# W5500.net
KiCad netlist of a schematic drawn in Altium Designer
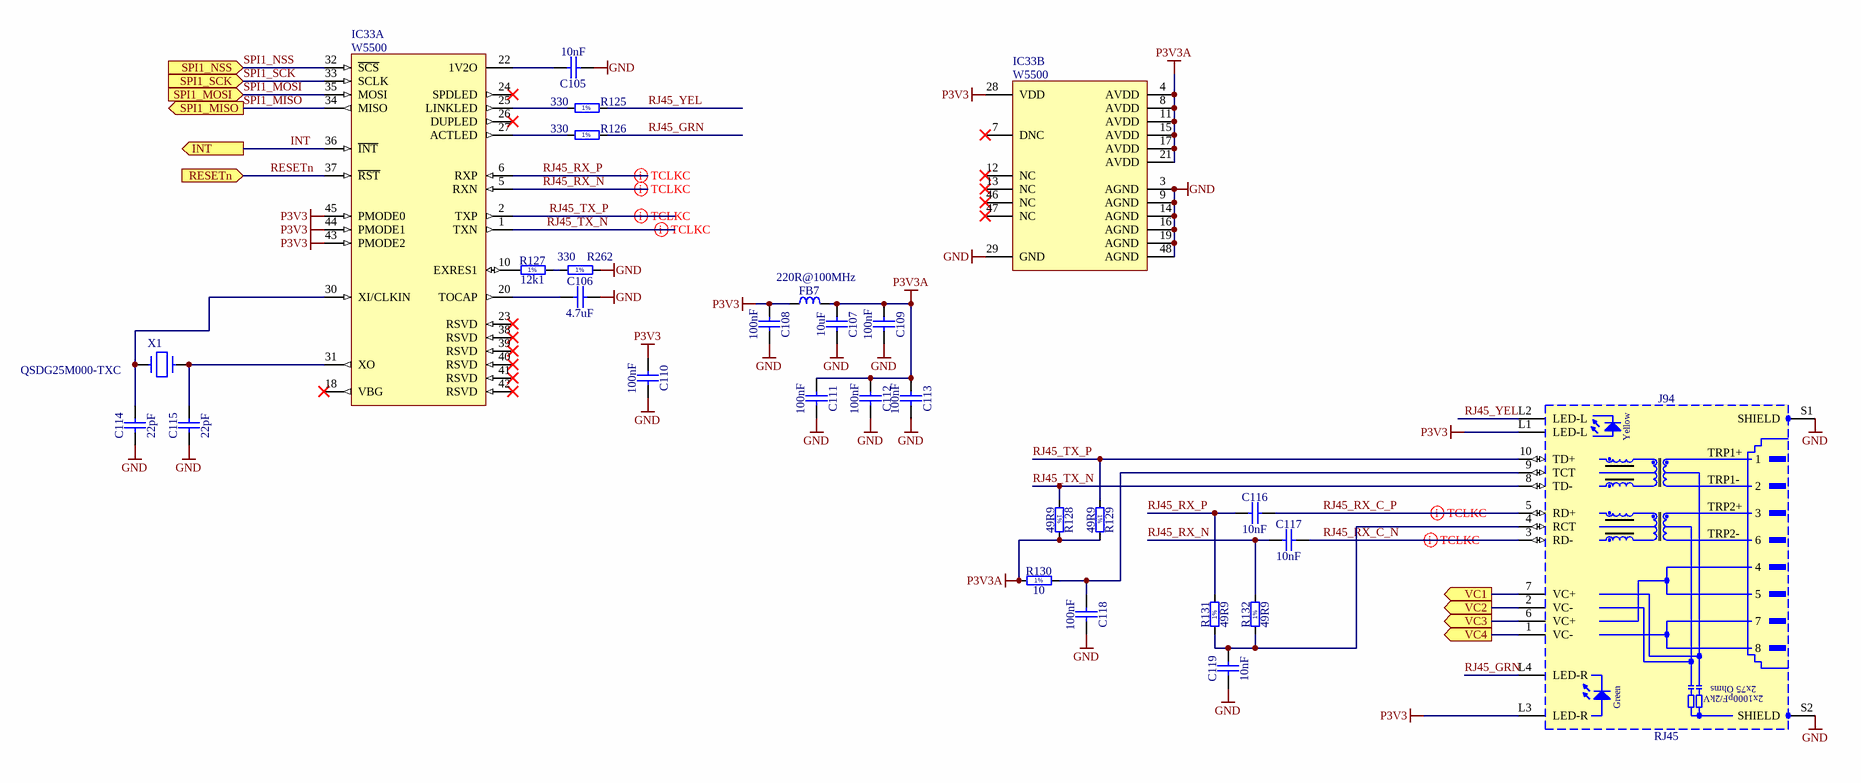
[diagram p0: W5500.SchDoc]

(export (version "E")
  (design (tool "Eeschema 10.0.6"))
  (components
    (comp (ref "C105")
      (value "10nF")
      (footprint "CAPC1608X87N")
      (description "Non-polarised capacitor")
      (fields
        (field (name "PART NUMBER") "CC0603_10NF_50V_5%_C0G")
        (field (name "VOLTAGE") "50V")
        (field (name "AUTHOR") "CERN DEM JLC")
      )
      (libsource (lib "Capacitors") (part "Capacitor - non polarized"))
    )
    (comp (ref "C106")
      (value "4.7uF")
      (footprint "CAPC1608X90N")
      (description "Non-polarised capacitor")
      (fields
        (field (name "PART NUMBER") "CC0603_4.7UF_25V_10%_X5R")
        (field (name "VOLTAGE") "25V")
        (field (name "AUTHOR") "CERN DEM JLC")
      )
      (libsource (lib "Capacitors") (part "Capacitor - non polarized"))
    )
    (comp (ref "C107")
      (value "10uF")
      (footprint "CAPC2012X135N")
      (description "Non-polarised capacitor")
      (fields
        (field (name "PART NUMBER") "CC0805_10UF_16V_10%_X5R")
        (field (name "VOLTAGE") "16V")
        (field (name "AUTHOR") "CERN DEM JLC")
      )
      (libsource (lib "Capacitors") (part "Capacitor - non polarized"))
    )
    (comp (ref "C108")
      (value "100nF")
      (footprint "CAPC1005X55N")
      (description "Non-polarised capacitor")
      (fields
        (field (name "PART NUMBER") "CC0402_100NF_16V_10%_X7R")
        (field (name "VOLTAGE") "16V")
        (field (name "AUTHOR") "CERN DEM JLC")
      )
      (libsource (lib "Capacitors") (part "Capacitor - non polarized"))
    )
    (comp (ref "C109")
      (value "100nF")
      (footprint "CAPC1005X55N")
      (description "Non-polarised capacitor")
      (fields
        (field (name "PART NUMBER") "CC0402_100NF_16V_10%_X7R")
        (field (name "VOLTAGE") "16V")
        (field (name "AUTHOR") "CERN DEM JLC")
      )
      (libsource (lib "Capacitors") (part "Capacitor - non polarized"))
    )
    (comp (ref "C110")
      (value "100nF")
      (footprint "CAPC1005X55N")
      (description "Non-polarised capacitor")
      (fields
        (field (name "PART NUMBER") "CC0402_100NF_16V_10%_X7R")
        (field (name "VOLTAGE") "16V")
        (field (name "AUTHOR") "CERN DEM JLC")
      )
      (libsource (lib "Capacitors") (part "Capacitor - non polarized"))
    )
    (comp (ref "C111")
      (value "100nF")
      (footprint "CAPC1005X55N")
      (description "Non-polarised capacitor")
      (fields
        (field (name "PART NUMBER") "CC0402_100NF_16V_10%_X7R")
        (field (name "VOLTAGE") "16V")
        (field (name "AUTHOR") "CERN DEM JLC")
      )
      (libsource (lib "Capacitors") (part "Capacitor - non polarized"))
    )
    (comp (ref "C112")
      (value "100nF")
      (footprint "CAPC1005X55N")
      (description "Non-polarised capacitor")
      (fields
        (field (name "PART NUMBER") "CC0402_100NF_16V_10%_X7R")
        (field (name "VOLTAGE") "16V")
        (field (name "AUTHOR") "CERN DEM JLC")
      )
      (libsource (lib "Capacitors") (part "Capacitor - non polarized"))
    )
    (comp (ref "C113")
      (value "100nF")
      (footprint "CAPC1005X55N")
      (description "Non-polarised capacitor")
      (fields
        (field (name "PART NUMBER") "CC0402_100NF_16V_10%_X7R")
        (field (name "VOLTAGE") "16V")
        (field (name "AUTHOR") "CERN DEM JLC")
      )
      (libsource (lib "Capacitors") (part "Capacitor - non polarized"))
    )
    (comp (ref "C114")
      (value "22pF")
      (footprint "CAPC1005X55N")
      (description "Non-polarised capacitor")
      (fields
        (field (name "PART NUMBER") "CC0402_22PF_50V_5%_NP0")
        (field (name "VOLTAGE") "50V")
        (field (name "AUTHOR") "CERN DEM JLC")
      )
      (libsource (lib "Capacitors") (part "Capacitor - non polarized"))
    )
    (comp (ref "C115")
      (value "22pF")
      (footprint "CAPC1005X55N")
      (description "Non-polarised capacitor")
      (fields
        (field (name "PART NUMBER") "CC0402_22PF_50V_5%_NP0")
        (field (name "VOLTAGE") "50V")
        (field (name "AUTHOR") "CERN DEM JLC")
      )
      (libsource (lib "Capacitors") (part "Capacitor - non polarized"))
    )
    (comp (ref "C116")
      (value "10nF")
      (footprint "CAPC1608X87N")
      (description "Non-polarised capacitor")
      (fields
        (field (name "PART NUMBER") "CC0603_10NF_50V_5%_C0G")
        (field (name "VOLTAGE") "50V")
        (field (name "AUTHOR") "CERN DEM JLC")
      )
      (libsource (lib "Capacitors") (part "Capacitor - non polarized"))
    )
    (comp (ref "C117")
      (value "10nF")
      (footprint "CAPC1608X87N")
      (description "Non-polarised capacitor")
      (fields
        (field (name "PART NUMBER") "CC0603_10NF_50V_5%_C0G")
        (field (name "VOLTAGE") "50V")
        (field (name "AUTHOR") "CERN DEM JLC")
      )
      (libsource (lib "Capacitors") (part "Capacitor - non polarized"))
    )
    (comp (ref "C118")
      (value "100nF")
      (footprint "CAPC1005X55N")
      (description "Non-polarised capacitor")
      (fields
        (field (name "PART NUMBER") "CC0402_100NF_16V_10%_X7R")
        (field (name "VOLTAGE") "16V")
        (field (name "AUTHOR") "CERN DEM JLC")
      )
      (libsource (lib "Capacitors") (part "Capacitor - non polarized"))
    )
    (comp (ref "C119")
      (value "10nF")
      (footprint "CAPC1608X87N")
      (description "Non-polarised capacitor")
      (fields
        (field (name "PART NUMBER") "CC0603_10NF_50V_5%_C0G")
        (field (name "VOLTAGE") "50V")
        (field (name "AUTHOR") "CERN DEM JLC")
      )
      (libsource (lib "Capacitors") (part "Capacitor - non polarized"))
    )
    (comp (ref "FB7")
      (value "220R@100MHz")
      (footprint "INDC2012X105N")
      (description "Inductor")
      (fields
        (field (name "PART NUMBER") "IND0805_MURATA_BLM21PG221SN1D")
        (field (name "POWER") "2A")
        (field (name "AUTHOR") "CERN DEM JLC")
      )
      (libsource (lib "Inductors & Transformers") (part "Inductor"))
    )
    (comp (ref "IC33")
      (value "W5500")
      (footprint "QFP50P900X900X160-48N")
      (description "iEthernet W5500 TCP/IP Performance and High Speed SPI Ethernet Controller")
      (fields (field (name "MANUFACTURER") "WIZNET") (field (name "AUTHOR") "CERN DEM MR"))
      (libsource (lib "ICs And Semiconductors") (part "W5500"))
    )
    (comp (ref "J94")
      (value "RJ45")
      (footprint "ABRACON_ARJM11C7-114-BA-EW2")
      (description "MagJack 10/100BaseT, PoE+, 1X1, OG/Y, -40 to 85*C, Tab Up, RoHS")
      (fields
        (field (name "PART NUMBER") "ARJM11C7-114-BA-EW2")
        (field (name "MANUFACTURER") "Abracon")
        (field (name "AUTHOR") "GK")
      )
      (libsource (lib "LIBRARY_SCH") (part "CON_ETH_POE_ARJM11C7"))
    )
    (comp (ref "R125")
      (value "330")
      (footprint "RESC1005X40N")
      (description "Resistor - 1%")
      (fields
        (field (name "PART NUMBER") "R0402_330R_1%_0.0625W_100PPM")
        (field (name "POWER") "0.0625W")
        (field (name "AUTHOR") "CERN DEM JLC")
      )
      (libsource (lib "Resistors") (part "Resistor - 1%"))
    )
    (comp (ref "R126")
      (value "330")
      (footprint "RESC1005X40N")
      (description "Resistor - 1%")
      (fields
        (field (name "PART NUMBER") "R0402_330R_1%_0.0625W_100PPM")
        (field (name "POWER") "0.0625W")
        (field (name "AUTHOR") "CERN DEM JLC")
      )
      (libsource (lib "Resistors") (part "Resistor - 1%"))
    )
    (comp (ref "R127")
      (value "12k1")
      (footprint "RESC1005X40N")
      (description "Resistor - 1%")
      (fields
        (field (name "PART NUMBER") "R0402_12K1_1%_0.0625W_100PPM")
        (field (name "POWER") "0.0625W")
        (field (name "AUTHOR") "CERN DEM JLC")
      )
      (libsource (lib "Resistors") (part "Resistor - 1%"))
    )
    (comp (ref "R128")
      (value "49R9")
      (footprint "RESC1005X40N")
      (description "Resistor - 1%")
      (fields
        (field (name "PART NUMBER") "R0402_49R9_1%_0.0625W_100PPM")
        (field (name "POWER") "0.0625W")
        (field (name "AUTHOR") "CERN DEM JLC")
      )
      (libsource (lib "Resistors") (part "Resistor - 1%"))
    )
    (comp (ref "R129")
      (value "49R9")
      (footprint "RESC1005X40N")
      (description "Resistor - 1%")
      (fields
        (field (name "PART NUMBER") "R0402_49R9_1%_0.0625W_100PPM")
        (field (name "POWER") "0.0625W")
        (field (name "AUTHOR") "CERN DEM JLC")
      )
      (libsource (lib "Resistors") (part "Resistor - 1%"))
    )
    (comp (ref "R130")
      (value "10")
      (footprint "RESC1005X40N")
      (description "Resistor - 1%")
      (fields
        (field (name "PART NUMBER") "R0402_10R_1%_0.0625W_200PPM")
        (field (name "POWER") "0.0625W")
        (field (name "AUTHOR") "CERN DEM JLC")
      )
      (libsource (lib "Resistors") (part "Resistor - 1%"))
    )
    (comp (ref "R131")
      (value "49R9")
      (footprint "RESC1005X40N")
      (description "Resistor - 1%")
      (fields
        (field (name "PART NUMBER") "R0402_49R9_1%_0.0625W_100PPM")
        (field (name "POWER") "0.0625W")
        (field (name "AUTHOR") "CERN DEM JLC")
      )
      (libsource (lib "Resistors") (part "Resistor - 1%"))
    )
    (comp (ref "R132")
      (value "49R9")
      (footprint "RESC1005X40N")
      (description "Resistor - 1%")
      (fields
        (field (name "PART NUMBER") "R0402_49R9_1%_0.0625W_100PPM")
        (field (name "POWER") "0.0625W")
        (field (name "AUTHOR") "CERN DEM JLC")
      )
      (libsource (lib "Resistors") (part "Resistor - 1%"))
    )
    (comp (ref "R262")
      (value "330")
      (footprint "RESC1005X40N")
      (description "Resistor - 1%")
      (fields
        (field (name "PART NUMBER") "R0402_330R_1%_0.0625W_100PPM")
        (field (name "POWER") "0.0625W")
        (field (name "AUTHOR") "CERN DEM JLC")
      )
      (libsource (lib "Resistors") (part "Resistor - 1%"))
    )
    (comp (ref "X1")
      (value "QSDG25M000-TXC")
      (footprint "XTAL_5.0*3.2")
      (description "miniature crystal oscillator (Maritex)")
      (libsource (lib "LIBRARY_SCH") (part "X_CRYSTAL_SMD_5.0*3.2"))
    )
  )
  (nets
    (net (code "1") (name "/INT") (class "Default")
      (node (ref "IC33") (pin "36") (pinfunction "~{INT}_36") (pintype "input"))
    )
    (net (code "2") (name "/RESETn") (class "Default")
      (node (ref "IC33") (pin "37") (pinfunction "~{RST}_37") (pintype "input"))
    )
    (net (code "3") (name "/RJ45_GRN") (class "Default")
      (node (ref "J94") (pin "L4") (pinfunction "LED-R_L4") (pintype "passive"))
      (node (ref "R126") (pin "2") (pinfunction "2_2") (pintype "passive"))
    )
    (net (code "4") (name "/RJ45_RX_C_N") (class "Default")
      (node (ref "C117") (pin "2") (pinfunction "2_2") (pintype "passive"))
      (node (ref "J94") (pin "3") (pinfunction "RD-_3") (pintype "bidirectional"))
    )
    (net (code "5") (name "/RJ45_RX_C_P") (class "Default")
      (node (ref "C116") (pin "2") (pinfunction "2_2") (pintype "passive"))
      (node (ref "J94") (pin "5") (pinfunction "RD+_5") (pintype "bidirectional"))
    )
    (net (code "6") (name "/RJ45_RX_N") (class "Default")
      (node (ref "C117") (pin "1") (pinfunction "1_1") (pintype "passive"))
      (node (ref "IC33") (pin "5") (pinfunction "RXN_5") (pintype "input"))
      (node (ref "R132") (pin "2") (pinfunction "2_2") (pintype "passive"))
    )
    (net (code "7") (name "/RJ45_RX_P") (class "Default")
      (node (ref "C116") (pin "1") (pinfunction "1_1") (pintype "passive"))
      (node (ref "IC33") (pin "6") (pinfunction "RXP_6") (pintype "input"))
      (node (ref "R131") (pin "2") (pinfunction "2_2") (pintype "passive"))
    )
    (net (code "8") (name "/RJ45_TX_N") (class "Default")
      (node (ref "IC33") (pin "1") (pinfunction "TXN_1") (pintype "output"))
      (node (ref "J94") (pin "8") (pinfunction "TD-_8") (pintype "bidirectional"))
      (node (ref "R128") (pin "1") (pinfunction "1_1") (pintype "passive"))
    )
    (net (code "9") (name "/RJ45_TX_P") (class "Default")
      (node (ref "IC33") (pin "2") (pinfunction "TXP_2") (pintype "output"))
      (node (ref "J94") (pin "10") (pinfunction "TD+_10") (pintype "bidirectional"))
      (node (ref "R129") (pin "1") (pinfunction "1_1") (pintype "passive"))
    )
    (net (code "10") (name "/RJ45_YEL") (class "Default")
      (node (ref "J94") (pin "L2") (pinfunction "LED-L_L2") (pintype "passive"))
      (node (ref "R125") (pin "2") (pinfunction "2_2") (pintype "passive"))
    )
    (net (code "11") (name "/SPI1_MISO") (class "Default")
      (node (ref "IC33") (pin "34") (pinfunction "MISO_34") (pintype "output"))
    )
    (net (code "12") (name "/SPI1_MOSI") (class "Default")
      (node (ref "IC33") (pin "35") (pinfunction "MOSI_35") (pintype "input"))
    )
    (net (code "13") (name "/SPI1_NSS") (class "Default")
      (node (ref "IC33") (pin "32") (pinfunction "~{SCS}_32") (pintype "input"))
    )
    (net (code "14") (name "/SPI1_SCK") (class "Default")
      (node (ref "IC33") (pin "33") (pinfunction "SCLK_33") (pintype "input"))
    )
    (net (code "15") (name "/VC1") (class "Default")
      (node (ref "J94") (pin "7") (pinfunction "VC+_7") (pintype "passive"))
    )
    (net (code "16") (name "/VC2") (class "Default")
      (node (ref "J94") (pin "2") (pinfunction "VC-_2") (pintype "passive"))
    )
    (net (code "17") (name "/VC3") (class "Default")
      (node (ref "J94") (pin "6") (pinfunction "VC+_6") (pintype "passive"))
    )
    (net (code "18") (name "/VC4") (class "Default")
      (node (ref "J94") (pin "1") (pinfunction "VC-_1") (pintype "passive"))
    )
    (net (code "19") (name "GND") (class "Default")
      (node (ref "C105") (pin "1") (pinfunction "1_1") (pintype "passive"))
      (node (ref "C106") (pin "2") (pinfunction "2_2") (pintype "passive"))
      (node (ref "C107") (pin "2") (pinfunction "2_2") (pintype "passive"))
      (node (ref "C108") (pin "2") (pinfunction "2_2") (pintype "passive"))
      (node (ref "C109") (pin "2") (pinfunction "2_2") (pintype "passive"))
      (node (ref "C110") (pin "2") (pinfunction "2_2") (pintype "passive"))
      (node (ref "C111") (pin "2") (pinfunction "2_2") (pintype "passive"))
      (node (ref "C112") (pin "2") (pinfunction "2_2") (pintype "passive"))
      (node (ref "C113") (pin "2") (pinfunction "2_2") (pintype "passive"))
      (node (ref "C114") (pin "1") (pinfunction "1_1") (pintype "passive"))
      (node (ref "C115") (pin "1") (pinfunction "1_1") (pintype "passive"))
      (node (ref "C118") (pin "2") (pinfunction "2_2") (pintype "passive"))
      (node (ref "C119") (pin "1") (pinfunction "1_1") (pintype "passive"))
      (node (ref "IC33") (pin "14") (pinfunction "AGND_14") (pintype "power_in"))
      (node (ref "IC33") (pin "16") (pinfunction "AGND_16") (pintype "power_in"))
      (node (ref "IC33") (pin "19") (pinfunction "AGND_19") (pintype "power_in"))
      (node (ref "IC33") (pin "29") (pinfunction "GND_29") (pintype "power_in"))
      (node (ref "IC33") (pin "3") (pinfunction "AGND_3") (pintype "power_in"))
      (node (ref "IC33") (pin "48") (pinfunction "AGND_48") (pintype "power_in"))
      (node (ref "IC33") (pin "9") (pinfunction "AGND_9") (pintype "power_in"))
      (node (ref "J94") (pin "S1") (pinfunction "SHIELD_S1") (pintype "power_in"))
      (node (ref "J94") (pin "S2") (pinfunction "SHIELD_S2") (pintype "power_in"))
      (node (ref "R262") (pin "2") (pinfunction "2_2") (pintype "passive"))
    )
    (net (code "20") (name "Net-(IC33A-1V2O)") (class "Default")
      (node (ref "C105") (pin "2") (pinfunction "2_2") (pintype "passive"))
      (node (ref "IC33") (pin "22") (pinfunction "1V2O_22") (pintype "power_in"))
    )
    (net (code "21") (name "Net-(IC33A-ACTLED)") (class "Default")
      (node (ref "IC33") (pin "27") (pinfunction "ACTLED_27") (pintype "output"))
      (node (ref "R126") (pin "1") (pinfunction "1_1") (pintype "passive"))
    )
    (net (code "22") (name "Net-(IC33A-EXRES1)") (class "Default")
      (node (ref "IC33") (pin "10") (pinfunction "EXRES1_10") (pintype "bidirectional"))
      (node (ref "R127") (pin "1") (pinfunction "1_1") (pintype "passive"))
    )
    (net (code "23") (name "Net-(IC33A-LINKLED)") (class "Default")
      (node (ref "IC33") (pin "25") (pinfunction "LINKLED_25") (pintype "output"))
      (node (ref "R125") (pin "1") (pinfunction "1_1") (pintype "passive"))
    )
    (net (code "24") (name "Net-(IC33A-TOCAP)") (class "Default")
      (node (ref "C106") (pin "1") (pinfunction "1_1") (pintype "passive"))
      (node (ref "IC33") (pin "20") (pinfunction "TOCAP_20") (pintype "output"))
    )
    (net (code "25") (name "Net-(IC33A-XI{slash}CLKIN)") (class "Default")
      (node (ref "C114") (pin "2") (pinfunction "2_2") (pintype "passive"))
      (node (ref "IC33") (pin "30") (pinfunction "XI/CLKIN_30") (pintype "input"))
      (node (ref "X1") (pin "1") (pinfunction "1_1") (pintype "passive"))
    )
    (net (code "26") (name "Net-(IC33A-XO)") (class "Default")
      (node (ref "C115") (pin "2") (pinfunction "2_2") (pintype "passive"))
      (node (ref "IC33") (pin "31") (pinfunction "XO_31") (pintype "output"))
      (node (ref "X1") (pin "2") (pinfunction "2_2") (pintype "passive"))
    )
    (net (code "27") (name "Net-(J94-RCT)") (class "Default")
      (node (ref "C119") (pin "2") (pinfunction "2_2") (pintype "passive"))
      (node (ref "J94") (pin "4") (pinfunction "RCT_4") (pintype "bidirectional"))
      (node (ref "R131") (pin "1") (pinfunction "1_1") (pintype "passive"))
      (node (ref "R132") (pin "1") (pinfunction "1_1") (pintype "passive"))
    )
    (net (code "28") (name "Net-(J94-TCT)") (class "Default")
      (node (ref "C118") (pin "1") (pinfunction "1_1") (pintype "passive"))
      (node (ref "J94") (pin "9") (pinfunction "TCT_9") (pintype "bidirectional"))
      (node (ref "R130") (pin "2") (pinfunction "2_2") (pintype "passive"))
    )
    (net (code "29") (name "Net-(R127-Pad2)") (class "Default")
      (node (ref "R127") (pin "2") (pinfunction "2_2") (pintype "passive"))
      (node (ref "R262") (pin "1") (pinfunction "1_1") (pintype "passive"))
    )
    (net (code "30") (name "P3V3") (class "Default")
      (node (ref "C108") (pin "1") (pinfunction "1_1") (pintype "passive"))
      (node (ref "C110") (pin "1") (pinfunction "1_1") (pintype "passive"))
      (node (ref "FB7") (pin "1") (pinfunction "1_1") (pintype "passive"))
      (node (ref "IC33") (pin "28") (pinfunction "VDD_28") (pintype "power_in"))
      (node (ref "IC33") (pin "43") (pinfunction "PMODE2_43") (pintype "input"))
      (node (ref "IC33") (pin "44") (pinfunction "PMODE1_44") (pintype "input"))
      (node (ref "IC33") (pin "45") (pinfunction "PMODE0_45") (pintype "input"))
      (node (ref "J94") (pin "L1") (pinfunction "LED-L_L1") (pintype "passive"))
      (node (ref "J94") (pin "L3") (pinfunction "LED-R_L3") (pintype "passive"))
    )
    (net (code "31") (name "P3V3A") (class "Default")
      (node (ref "C107") (pin "1") (pinfunction "1_1") (pintype "passive"))
      (node (ref "C109") (pin "1") (pinfunction "1_1") (pintype "passive"))
      (node (ref "C111") (pin "1") (pinfunction "1_1") (pintype "passive"))
      (node (ref "C112") (pin "1") (pinfunction "1_1") (pintype "passive"))
      (node (ref "C113") (pin "1") (pinfunction "1_1") (pintype "passive"))
      (node (ref "FB7") (pin "2") (pinfunction "2_2") (pintype "passive"))
      (node (ref "IC33") (pin "11") (pinfunction "AVDD_11") (pintype "power_in"))
      (node (ref "IC33") (pin "15") (pinfunction "AVDD_15") (pintype "power_in"))
      (node (ref "IC33") (pin "17") (pinfunction "AVDD_17") (pintype "power_in"))
      (node (ref "IC33") (pin "21") (pinfunction "AVDD_21") (pintype "power_in"))
      (node (ref "IC33") (pin "4") (pinfunction "AVDD_4") (pintype "power_in"))
      (node (ref "IC33") (pin "8") (pinfunction "AVDD_8") (pintype "power_in"))
      (node (ref "R128") (pin "2") (pinfunction "2_2") (pintype "passive"))
      (node (ref "R129") (pin "2") (pinfunction "2_2") (pintype "passive"))
      (node (ref "R130") (pin "1") (pinfunction "1_1") (pintype "passive"))
    )
    (net (code "32") (name "unconnected-(IC33A-DUPLED-Pad26)") (class "Default")
      (node (ref "IC33") (pin "26") (pinfunction "DUPLED_26") (pintype "output+no_connect"))
    )
    (net (code "33") (name "unconnected-(IC33A-RSVD-Pad23)") (class "Default")
      (node (ref "IC33") (pin "23") (pinfunction "RSVD_23") (pintype "input+no_connect"))
    )
    (net (code "34") (name "unconnected-(IC33A-RSVD-Pad38)") (class "Default")
      (node (ref "IC33") (pin "38") (pinfunction "RSVD_38") (pintype "input+no_connect"))
    )
    (net (code "35") (name "unconnected-(IC33A-RSVD-Pad39)") (class "Default")
      (node (ref "IC33") (pin "39") (pinfunction "RSVD_39") (pintype "input+no_connect"))
    )
    (net (code "36") (name "unconnected-(IC33A-RSVD-Pad40)") (class "Default")
      (node (ref "IC33") (pin "40") (pinfunction "RSVD_40") (pintype "input+no_connect"))
    )
    (net (code "37") (name "unconnected-(IC33A-RSVD-Pad41)") (class "Default")
      (node (ref "IC33") (pin "41") (pinfunction "RSVD_41") (pintype "input+no_connect"))
    )
    (net (code "38") (name "unconnected-(IC33A-RSVD-Pad42)") (class "Default")
      (node (ref "IC33") (pin "42") (pinfunction "RSVD_42") (pintype "input+no_connect"))
    )
    (net (code "39") (name "unconnected-(IC33A-SPDLED-Pad24)") (class "Default")
      (node (ref "IC33") (pin "24") (pinfunction "SPDLED_24") (pintype "output+no_connect"))
    )
    (net (code "40") (name "unconnected-(IC33A-VBG-Pad18)") (class "Default")
      (node (ref "IC33") (pin "18") (pinfunction "VBG_18") (pintype "output+no_connect"))
    )
    (net (code "41") (name "unconnected-(IC33B-DNC-Pad7)") (class "Default")
      (node (ref "IC33") (pin "7") (pinfunction "DNC_7") (pintype "passive+no_connect"))
    )
    (net (code "42") (name "unconnected-(IC33B-NC-Pad12)") (class "Default")
      (node (ref "IC33") (pin "12") (pinfunction "NC_12") (pintype "passive+no_connect"))
    )
    (net (code "43") (name "unconnected-(IC33B-NC-Pad13)") (class "Default")
      (node (ref "IC33") (pin "13") (pinfunction "NC_13") (pintype "passive+no_connect"))
    )
    (net (code "44") (name "unconnected-(IC33B-NC-Pad46)") (class "Default")
      (node (ref "IC33") (pin "46") (pinfunction "NC_46") (pintype "passive+no_connect"))
    )
    (net (code "45") (name "unconnected-(IC33B-NC-Pad47)") (class "Default")
      (node (ref "IC33") (pin "47") (pinfunction "NC_47") (pintype "passive+no_connect"))
    )
  )
)
